# Programmer_Board_v1_Tests.net
KiCad netlist of a schematic drawn in EAGLE
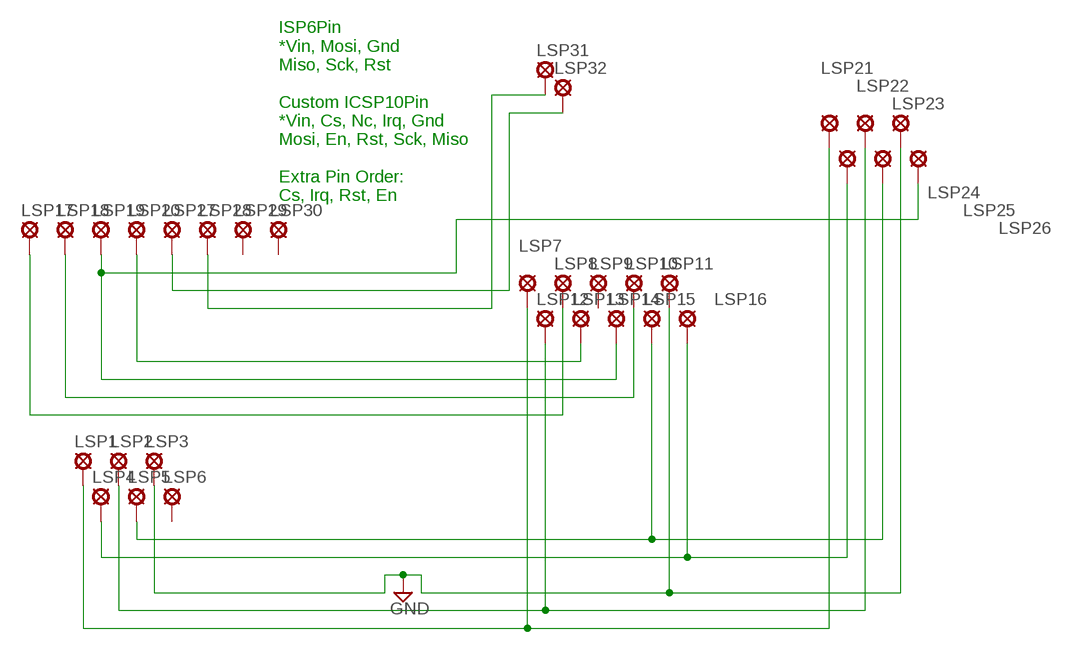
[diagram p0: schematic, sheet 1]

(export (version "E")
  (design (tool "Eeschema 10.0.6"))
  (components
    (comp (ref "LSP1")
      (value "LSP10_CLSP10_C")
      (footprint "eagle-import:LSP10_C")
      (libsource (lib "eagle-import") (part "LSP10_CLSP10_C"))
    )
    (comp (ref "LSP2")
      (value "LSP10_CLSP10_C")
      (footprint "eagle-import:LSP10_C")
      (libsource (lib "eagle-import") (part "LSP10_CLSP10_C"))
    )
    (comp (ref "LSP3")
      (value "LSP10_CLSP10_C")
      (footprint "eagle-import:LSP10_C")
      (libsource (lib "eagle-import") (part "LSP10_CLSP10_C"))
    )
    (comp (ref "LSP4")
      (value "LSP10_CLSP10_C")
      (footprint "eagle-import:LSP10_C")
      (libsource (lib "eagle-import") (part "LSP10_CLSP10_C"))
    )
    (comp (ref "LSP5")
      (value "LSP10_CLSP10_C")
      (footprint "eagle-import:LSP10_C")
      (libsource (lib "eagle-import") (part "LSP10_CLSP10_C"))
    )
    (comp (ref "LSP6")
      (value "LSP10_CLSP10_C")
      (footprint "eagle-import:LSP10_C")
      (libsource (lib "eagle-import") (part "LSP10_CLSP10_C"))
    )
    (comp (ref "LSP7")
      (value "LSP10_CLSP10_C")
      (footprint "eagle-import:LSP10_C")
      (libsource (lib "eagle-import") (part "LSP10_CLSP10_C"))
    )
    (comp (ref "LSP8")
      (value "LSP10_CLSP10_C")
      (footprint "eagle-import:LSP10_C")
      (libsource (lib "eagle-import") (part "LSP10_CLSP10_C"))
    )
    (comp (ref "LSP9")
      (value "LSP10_CLSP10_C")
      (footprint "eagle-import:LSP10_C")
      (libsource (lib "eagle-import") (part "LSP10_CLSP10_C"))
    )
    (comp (ref "LSP10")
      (value "LSP10_CLSP10_C")
      (footprint "eagle-import:LSP10_C")
      (libsource (lib "eagle-import") (part "LSP10_CLSP10_C"))
    )
    (comp (ref "LSP11")
      (value "LSP10_CLSP10_C")
      (footprint "eagle-import:LSP10_C")
      (libsource (lib "eagle-import") (part "LSP10_CLSP10_C"))
    )
    (comp (ref "LSP12")
      (value "LSP10_CLSP10_C")
      (footprint "eagle-import:LSP10_C")
      (libsource (lib "eagle-import") (part "LSP10_CLSP10_C"))
    )
    (comp (ref "LSP13")
      (value "LSP10_CLSP10_C")
      (footprint "eagle-import:LSP10_C")
      (libsource (lib "eagle-import") (part "LSP10_CLSP10_C"))
    )
    (comp (ref "LSP14")
      (value "LSP10_CLSP10_C")
      (footprint "eagle-import:LSP10_C")
      (libsource (lib "eagle-import") (part "LSP10_CLSP10_C"))
    )
    (comp (ref "LSP15")
      (value "LSP10_CLSP10_C")
      (footprint "eagle-import:LSP10_C")
      (libsource (lib "eagle-import") (part "LSP10_CLSP10_C"))
    )
    (comp (ref "LSP16")
      (value "LSP10_CLSP10_C")
      (footprint "eagle-import:LSP10_C")
      (libsource (lib "eagle-import") (part "LSP10_CLSP10_C"))
    )
    (comp (ref "LSP17")
      (value "LSP10_CLSP10_C")
      (footprint "eagle-import:LSP10_C")
      (libsource (lib "eagle-import") (part "LSP10_CLSP10_C"))
    )
    (comp (ref "LSP18")
      (value "LSP10_CLSP10_C")
      (footprint "eagle-import:LSP10_C")
      (libsource (lib "eagle-import") (part "LSP10_CLSP10_C"))
    )
    (comp (ref "LSP19")
      (value "LSP10_CLSP10_C")
      (footprint "eagle-import:LSP10_C")
      (libsource (lib "eagle-import") (part "LSP10_CLSP10_C"))
    )
    (comp (ref "LSP20")
      (value "LSP10_CLSP10_C")
      (footprint "eagle-import:LSP10_C")
      (libsource (lib "eagle-import") (part "LSP10_CLSP10_C"))
    )
    (comp (ref "LSP21")
      (value "LSP10_CLSP10_C")
      (footprint "eagle-import:LSP10_C")
      (libsource (lib "eagle-import") (part "LSP10_CLSP10_C"))
    )
    (comp (ref "LSP22")
      (value "LSP10_CLSP10_C")
      (footprint "eagle-import:LSP10_C")
      (libsource (lib "eagle-import") (part "LSP10_CLSP10_C"))
    )
    (comp (ref "LSP23")
      (value "LSP10_CLSP10_C")
      (footprint "eagle-import:LSP10_C")
      (libsource (lib "eagle-import") (part "LSP10_CLSP10_C"))
    )
    (comp (ref "LSP24")
      (value "LSP10_CLSP10_C")
      (footprint "eagle-import:LSP10_C")
      (libsource (lib "eagle-import") (part "LSP10_CLSP10_C"))
    )
    (comp (ref "LSP25")
      (value "LSP10_CLSP10_C")
      (footprint "eagle-import:LSP10_C")
      (libsource (lib "eagle-import") (part "LSP10_CLSP10_C"))
    )
    (comp (ref "LSP26")
      (value "LSP10_CLSP10_C")
      (footprint "eagle-import:LSP10_C")
      (libsource (lib "eagle-import") (part "LSP10_CLSP10_C"))
    )
    (comp (ref "LSP27")
      (value "LSP10_CLSP10_C")
      (footprint "eagle-import:LSP10_C")
      (libsource (lib "eagle-import") (part "LSP10_CLSP10_C"))
    )
    (comp (ref "LSP28")
      (value "LSP10_CLSP10_C")
      (footprint "eagle-import:LSP10_C")
      (libsource (lib "eagle-import") (part "LSP10_CLSP10_C"))
    )
    (comp (ref "LSP29")
      (value "LSP10_CLSP10_C")
      (footprint "eagle-import:LSP10_C")
      (libsource (lib "eagle-import") (part "LSP10_CLSP10_C"))
    )
    (comp (ref "LSP30")
      (value "LSP10_CLSP10_C")
      (footprint "eagle-import:LSP10_C")
      (libsource (lib "eagle-import") (part "LSP10_CLSP10_C"))
    )
    (comp (ref "LSP31")
      (value "LSP10_CLSP10_C")
      (footprint "eagle-import:LSP10_C")
      (libsource (lib "eagle-import") (part "LSP10_CLSP10_C"))
    )
    (comp (ref "LSP32")
      (value "LSP10_CLSP10_C")
      (footprint "eagle-import:LSP10_C")
      (libsource (lib "eagle-import") (part "LSP10_CLSP10_C"))
    )
  )
  (nets
    (net (code "1") (name "GND") (class "Default")
      (node (ref "LSP11") (pin "P$1") (pinfunction "MP_P$1") (pintype "passive"))
      (node (ref "LSP23") (pin "P$1") (pinfunction "MP_P$1") (pintype "passive"))
      (node (ref "LSP3") (pin "P$1") (pinfunction "MP_P$1") (pintype "passive"))
    )
    (net (code "2") (name "Net-(LSP1-MP)") (class "Default")
      (node (ref "LSP1") (pin "P$1") (pinfunction "MP_P$1") (pintype "passive"))
      (node (ref "LSP21") (pin "P$1") (pinfunction "MP_P$1") (pintype "passive"))
      (node (ref "LSP7") (pin "P$1") (pinfunction "MP_P$1") (pintype "passive"))
    )
    (net (code "3") (name "Net-(LSP10-MP)") (class "Default")
      (node (ref "LSP10") (pin "P$1") (pinfunction "MP_P$1") (pintype "passive"))
      (node (ref "LSP18") (pin "P$1") (pinfunction "MP_P$1") (pintype "passive"))
    )
    (net (code "4") (name "Net-(LSP12-MP)") (class "Default")
      (node (ref "LSP12") (pin "P$1") (pinfunction "MP_P$1") (pintype "passive"))
      (node (ref "LSP2") (pin "P$1") (pinfunction "MP_P$1") (pintype "passive"))
      (node (ref "LSP22") (pin "P$1") (pinfunction "MP_P$1") (pintype "passive"))
    )
    (net (code "5") (name "Net-(LSP13-MP)") (class "Default")
      (node (ref "LSP13") (pin "P$1") (pinfunction "MP_P$1") (pintype "passive"))
      (node (ref "LSP20") (pin "P$1") (pinfunction "MP_P$1") (pintype "passive"))
    )
    (net (code "6") (name "Net-(LSP14-MP)") (class "Default")
      (node (ref "LSP14") (pin "P$1") (pinfunction "MP_P$1") (pintype "passive"))
      (node (ref "LSP19") (pin "P$1") (pinfunction "MP_P$1") (pintype "passive"))
      (node (ref "LSP26") (pin "P$1") (pinfunction "MP_P$1") (pintype "passive"))
    )
    (net (code "7") (name "Net-(LSP15-MP)") (class "Default")
      (node (ref "LSP15") (pin "P$1") (pinfunction "MP_P$1") (pintype "passive"))
      (node (ref "LSP25") (pin "P$1") (pinfunction "MP_P$1") (pintype "passive"))
      (node (ref "LSP5") (pin "P$1") (pinfunction "MP_P$1") (pintype "passive"))
    )
    (net (code "8") (name "Net-(LSP16-MP)") (class "Default")
      (node (ref "LSP16") (pin "P$1") (pinfunction "MP_P$1") (pintype "passive"))
      (node (ref "LSP24") (pin "P$1") (pinfunction "MP_P$1") (pintype "passive"))
      (node (ref "LSP4") (pin "P$1") (pinfunction "MP_P$1") (pintype "passive"))
    )
    (net (code "9") (name "Net-(LSP17-MP)") (class "Default")
      (node (ref "LSP17") (pin "P$1") (pinfunction "MP_P$1") (pintype "passive"))
      (node (ref "LSP8") (pin "P$1") (pinfunction "MP_P$1") (pintype "passive"))
    )
    (net (code "10") (name "Net-(LSP27-MP)") (class "Default")
      (node (ref "LSP27") (pin "P$1") (pinfunction "MP_P$1") (pintype "passive"))
      (node (ref "LSP32") (pin "P$1") (pinfunction "MP_P$1") (pintype "passive"))
    )
    (net (code "11") (name "Net-(LSP28-MP)") (class "Default")
      (node (ref "LSP28") (pin "P$1") (pinfunction "MP_P$1") (pintype "passive"))
      (node (ref "LSP31") (pin "P$1") (pinfunction "MP_P$1") (pintype "passive"))
    )
    (net (code "12") (name "unconnected-(LSP6-MP-PadP$1)") (class "Default")
      (node (ref "LSP6") (pin "P$1") (pinfunction "MP_P$1") (pintype "passive"))
    )
    (net (code "13") (name "unconnected-(LSP9-MP-PadP$1)") (class "Default")
      (node (ref "LSP9") (pin "P$1") (pinfunction "MP_P$1") (pintype "passive"))
    )
    (net (code "14") (name "unconnected-(LSP29-MP-PadP$1)") (class "Default")
      (node (ref "LSP29") (pin "P$1") (pinfunction "MP_P$1") (pintype "passive"))
    )
    (net (code "15") (name "unconnected-(LSP30-MP-PadP$1)") (class "Default")
      (node (ref "LSP30") (pin "P$1") (pinfunction "MP_P$1") (pintype "passive"))
    )
  )
)
